# T2008_thermometre.net
KiCad netlist of a schematic drawn in EAGLE
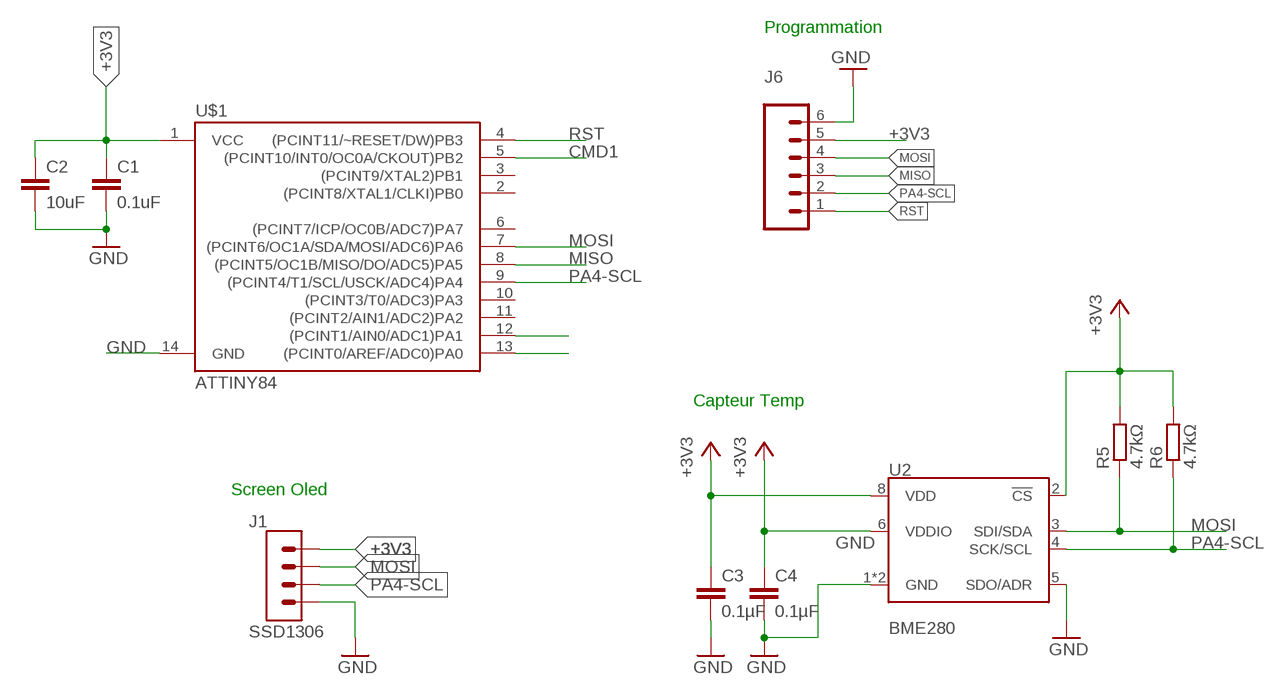
[diagram p0: schematic, sheet 1]

(export (version "E")
  (design (tool "Eeschema 10.0.6"))
  (components
    (comp (ref "C1")
      (value "0.1uF")
      (footprint "eagle-import:C0603K")
      (libsource (lib "eagle-import") (part "resistor_348_C-EUC0603K"))
    )
    (comp (ref "C2")
      (value "10uF")
      (footprint "eagle-import:C0603K")
      (libsource (lib "eagle-import") (part "resistor_348_C-EUC0603K"))
    )
    (comp (ref "C3")
      (value "0.1µF")
      (footprint "eagle-import:C0603K")
      (libsource (lib "eagle-import") (part "C-EUC0603K"))
    )
    (comp (ref "C4")
      (value "0.1µF")
      (footprint "eagle-import:C0603K")
      (libsource (lib "eagle-import") (part "C-EUC0603K"))
    )
    (comp (ref "J1")
      (value "SSD1306")
      (footprint "eagle-import:62000411121")
      (fields
        (field (name "MANUFACTURER") "Würth Elektronik ")
        (field (name "MPN") "62000411121")
        (field (name "CREATED_BY") "PCBLayout.com")
      )
      (libsource (lib "eagle-import") (part "62000411121"))
    )
    (comp (ref "J6")
      (value "CONN_06SMD_MALE")
      (footprint "eagle-import:1X06_SMD_MALE")
      (libsource (lib "eagle-import") (part "CONN_06SMD_MALE"))
    )
    (comp (ref "R5")
      (value "4.7kΩ")
      (footprint "eagle-import:R0603")
      (libsource (lib "eagle-import") (part "R-EU_R0603"))
    )
    (comp (ref "R6")
      (value "4.7kΩ")
      (footprint "eagle-import:R0603")
      (libsource (lib "eagle-import") (part "R-EU_R0603"))
    )
    (comp (ref "U$1")
      (value "ATTINY84")
      (footprint "eagle-import:SO14")
      (libsource (lib "eagle-import") (part "ATTINY84"))
    )
    (comp (ref "U2")
      (value "BME280")
      (footprint "eagle-import:LGA-8-2.5X2.5")
      (libsource (lib "eagle-import") (part "BME280"))
    )
  )
  (nets
    (net (code "1") (name "+3V3") (class "Default")
      (node (ref "C1") (pin "1") (pinfunction "1_1") (pintype "passive"))
      (node (ref "C2") (pin "1") (pinfunction "1_1") (pintype "passive"))
      (node (ref "C3") (pin "1") (pinfunction "1_1") (pintype "passive"))
      (node (ref "C4") (pin "1") (pinfunction "1_1") (pintype "passive"))
      (node (ref "J1") (pin "1") (pinfunction "1_1") (pintype "passive"))
      (node (ref "J6") (pin "5") (pinfunction "5_5") (pintype "passive"))
      (node (ref "R5") (pin "2") (pinfunction "2_2") (pintype "passive"))
      (node (ref "R6") (pin "2") (pinfunction "2_2") (pintype "passive"))
      (node (ref "U$1") (pin "1") (pinfunction "VCC_1") (pintype "bidirectional"))
      (node (ref "U2") (pin "2") (pinfunction "~{CS}_2") (pintype "bidirectional"))
      (node (ref "U2") (pin "6") (pinfunction "VDDIO_6") (pintype "bidirectional"))
      (node (ref "U2") (pin "8") (pinfunction "VDD_8") (pintype "bidirectional"))
    )
    (net (code "2") (name "/CMD1") (class "Default")
      (node (ref "U$1") (pin "5") (pinfunction "(PCINT10/INT0/OC0A/CKOUT)PB2_5") (pintype "bidirectional"))
    )
    (net (code "3") (name "GND") (class "Default")
      (node (ref "C1") (pin "2") (pinfunction "2_2") (pintype "passive"))
      (node (ref "C2") (pin "2") (pinfunction "2_2") (pintype "passive"))
      (node (ref "C3") (pin "2") (pinfunction "2_2") (pintype "passive"))
      (node (ref "C4") (pin "2") (pinfunction "2_2") (pintype "passive"))
      (node (ref "J1") (pin "4") (pinfunction "4_4") (pintype "passive"))
      (node (ref "J6") (pin "6") (pinfunction "6_6") (pintype "passive"))
      (node (ref "U$1") (pin "14") (pinfunction "GND_14") (pintype "bidirectional"))
      (node (ref "U2") (pin "1") (pinfunction "GND_1") (pintype "bidirectional"))
      (node (ref "U2") (pin "5") (pinfunction "SDO/ADR_5") (pintype "bidirectional"))
      (node (ref "U2") (pin "7") (pinfunction "GND_7") (pintype "bidirectional"))
    )
    (net (code "4") (name "MISO") (class "Default")
      (node (ref "J6") (pin "3") (pinfunction "3_3") (pintype "passive"))
      (node (ref "U$1") (pin "8") (pinfunction "(PCINT5/OC1B/MISO/DO/ADC5)PA5_8") (pintype "bidirectional"))
    )
    (net (code "5") (name "MOSI") (class "Default")
      (node (ref "J1") (pin "2") (pinfunction "2_2") (pintype "passive"))
      (node (ref "J6") (pin "4") (pinfunction "4_4") (pintype "passive"))
      (node (ref "R5") (pin "1") (pinfunction "1_1") (pintype "passive"))
      (node (ref "U$1") (pin "7") (pinfunction "(PCINT6/OC1A/SDA/MOSI/ADC6)PA6_7") (pintype "bidirectional"))
      (node (ref "U2") (pin "3") (pinfunction "SDI/SDA_3") (pintype "bidirectional"))
    )
    (net (code "6") (name "PA4-SCL") (class "Default")
      (node (ref "J1") (pin "3") (pinfunction "3_3") (pintype "passive"))
      (node (ref "J6") (pin "2") (pinfunction "2_2") (pintype "passive"))
      (node (ref "R6") (pin "1") (pinfunction "1_1") (pintype "passive"))
      (node (ref "U$1") (pin "9") (pinfunction "(PCINT4/T1/SCL/USCK/ADC4)PA4_9") (pintype "bidirectional"))
      (node (ref "U2") (pin "4") (pinfunction "SCK/SCL_4") (pintype "bidirectional"))
    )
    (net (code "7") (name "RST") (class "Default")
      (node (ref "J6") (pin "1") (pinfunction "1_1") (pintype "passive"))
      (node (ref "U$1") (pin "4") (pinfunction "(PCINT11/~{RESET/DW})PB3_4") (pintype "bidirectional"))
    )
    (net (code "8") (name "unconnected-(U$1-(PCINT0{slash}AREF{slash}ADC0)PA0-Pad13)") (class "Default")
      (node (ref "U$1") (pin "13") (pinfunction "(PCINT0/AREF/ADC0)PA0_13") (pintype "bidirectional"))
    )
    (net (code "9") (name "unconnected-(U$1-(PCINT1{slash}AIN0{slash}ADC1)PA1-Pad12)") (class "Default")
      (node (ref "U$1") (pin "12") (pinfunction "(PCINT1/AIN0/ADC1)PA1_12") (pintype "bidirectional"))
    )
    (net (code "10") (name "unconnected-(U$1-(PCINT2{slash}AIN1{slash}ADC2)PA2-Pad11)") (class "Default")
      (node (ref "U$1") (pin "11") (pinfunction "(PCINT2/AIN1/ADC2)PA2_11") (pintype "bidirectional"))
    )
    (net (code "11") (name "unconnected-(U$1-(PCINT3{slash}T0{slash}ADC3)PA3-Pad10)") (class "Default")
      (node (ref "U$1") (pin "10") (pinfunction "(PCINT3/T0/ADC3)PA3_10") (pintype "bidirectional"))
    )
    (net (code "12") (name "unconnected-(U$1-(PCINT7{slash}ICP{slash}OC0B{slash}ADC7)PA7-Pad6)") (class "Default")
      (node (ref "U$1") (pin "6") (pinfunction "(PCINT7/ICP/OC0B/ADC7)PA7_6") (pintype "bidirectional"))
    )
    (net (code "13") (name "unconnected-(U$1-(PCINT8{slash}XTAL1{slash}CLKI)PB0-Pad2)") (class "Default")
      (node (ref "U$1") (pin "2") (pinfunction "(PCINT8/XTAL1/CLKI)PB0_2") (pintype "bidirectional"))
    )
    (net (code "14") (name "unconnected-(U$1-(PCINT9{slash}XTAL2)PB1-Pad3)") (class "Default")
      (node (ref "U$1") (pin "3") (pinfunction "(PCINT9/XTAL2)PB1_3") (pintype "bidirectional"))
    )
  )
)
